# Program_Counter.net
KiCad netlist of a schematic drawn in Altium Designer
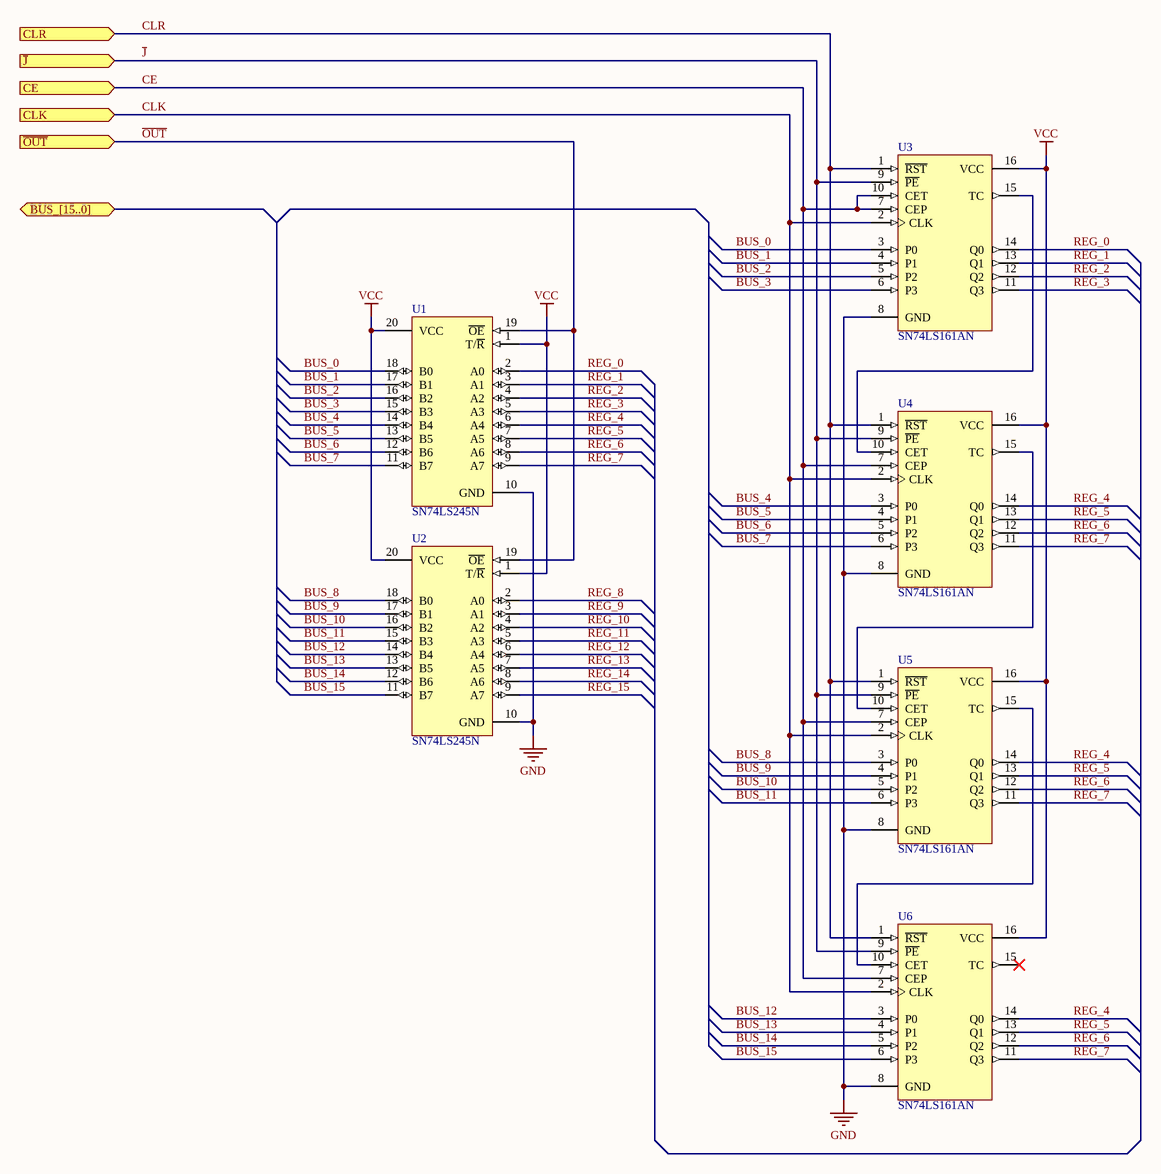
[diagram p0: Program_Counter.SchDoc]

(export (version "E")
  (design (tool "Eeschema 10.0.6"))
  (components
    (comp (ref "U1")
      (value "SN74LS245N")
      (footprint "N020")
      (description "Octal Bus Transceiver with 3-State Outputs")
      (fields (field (name "PUBLISHER") "Altium Limited"))
      (libsource (lib "TI Interface 8-Bit Line Transceiver") (part "SN74LS245N"))
    )
    (comp (ref "U2")
      (value "SN74LS245N")
      (footprint "N020")
      (description "Octal Bus Transceiver with 3-State Outputs")
      (fields (field (name "PUBLISHER") "Altium Limited"))
      (libsource (lib "TI Interface 8-Bit Line Transceiver") (part "SN74LS245N"))
    )
    (comp (ref "U3")
      (value "SN74LS161AN")
      (footprint "N016")
      (description "Synchronous 4-Bit Counter")
      (fields (field (name "PUBLISHER") "Altium Limited"))
      (libsource (lib "TI Logic Counter") (part "SN74LS161AN"))
    )
    (comp (ref "U4")
      (value "SN74LS161AN")
      (footprint "N016")
      (description "Synchronous 4-Bit Counter")
      (fields (field (name "PUBLISHER") "Altium Limited"))
      (libsource (lib "TI Logic Counter") (part "SN74LS161AN"))
    )
    (comp (ref "U5")
      (value "SN74LS161AN")
      (footprint "N016")
      (description "Synchronous 4-Bit Counter")
      (fields (field (name "PUBLISHER") "Altium Limited"))
      (libsource (lib "TI Logic Counter") (part "SN74LS161AN"))
    )
    (comp (ref "U6")
      (value "SN74LS161AN")
      (footprint "N016")
      (description "Synchronous 4-Bit Counter")
      (fields (field (name "PUBLISHER") "Altium Limited"))
      (libsource (lib "TI Logic Counter") (part "SN74LS161AN"))
    )
  )
  (nets
    (net (code "1") (name "/BUS_0") (class "Default")
      (node (ref "U1") (pin "18") (pinfunction "B0_18") (pintype "bidirectional"))
      (node (ref "U3") (pin "3") (pinfunction "P0_3") (pintype "input"))
    )
    (net (code "2") (name "/BUS_1") (class "Default")
      (node (ref "U1") (pin "17") (pinfunction "B1_17") (pintype "bidirectional"))
      (node (ref "U3") (pin "4") (pinfunction "P1_4") (pintype "input"))
    )
    (net (code "3") (name "/BUS_2") (class "Default")
      (node (ref "U1") (pin "16") (pinfunction "B2_16") (pintype "bidirectional"))
      (node (ref "U3") (pin "5") (pinfunction "P2_5") (pintype "input"))
    )
    (net (code "4") (name "/BUS_3") (class "Default")
      (node (ref "U1") (pin "15") (pinfunction "B3_15") (pintype "bidirectional"))
      (node (ref "U3") (pin "6") (pinfunction "P3_6") (pintype "input"))
    )
    (net (code "5") (name "/BUS_4") (class "Default")
      (node (ref "U1") (pin "14") (pinfunction "B4_14") (pintype "bidirectional"))
      (node (ref "U4") (pin "3") (pinfunction "P0_3") (pintype "input"))
    )
    (net (code "6") (name "/BUS_5") (class "Default")
      (node (ref "U1") (pin "13") (pinfunction "B5_13") (pintype "bidirectional"))
      (node (ref "U4") (pin "4") (pinfunction "P1_4") (pintype "input"))
    )
    (net (code "7") (name "/BUS_6") (class "Default")
      (node (ref "U1") (pin "12") (pinfunction "B6_12") (pintype "bidirectional"))
      (node (ref "U4") (pin "5") (pinfunction "P2_5") (pintype "input"))
    )
    (net (code "8") (name "/BUS_7") (class "Default")
      (node (ref "U1") (pin "11") (pinfunction "B7_11") (pintype "bidirectional"))
      (node (ref "U4") (pin "6") (pinfunction "P3_6") (pintype "input"))
    )
    (net (code "9") (name "/BUS_8") (class "Default")
      (node (ref "U2") (pin "18") (pinfunction "B0_18") (pintype "bidirectional"))
      (node (ref "U5") (pin "3") (pinfunction "P0_3") (pintype "input"))
    )
    (net (code "10") (name "/BUS_9") (class "Default")
      (node (ref "U2") (pin "17") (pinfunction "B1_17") (pintype "bidirectional"))
      (node (ref "U5") (pin "4") (pinfunction "P1_4") (pintype "input"))
    )
    (net (code "11") (name "/BUS_10") (class "Default")
      (node (ref "U2") (pin "16") (pinfunction "B2_16") (pintype "bidirectional"))
      (node (ref "U5") (pin "5") (pinfunction "P2_5") (pintype "input"))
    )
    (net (code "12") (name "/BUS_11") (class "Default")
      (node (ref "U2") (pin "15") (pinfunction "B3_15") (pintype "bidirectional"))
      (node (ref "U5") (pin "6") (pinfunction "P3_6") (pintype "input"))
    )
    (net (code "13") (name "/BUS_12") (class "Default")
      (node (ref "U2") (pin "14") (pinfunction "B4_14") (pintype "bidirectional"))
      (node (ref "U6") (pin "3") (pinfunction "P0_3") (pintype "input"))
    )
    (net (code "14") (name "/BUS_13") (class "Default")
      (node (ref "U2") (pin "13") (pinfunction "B5_13") (pintype "bidirectional"))
      (node (ref "U6") (pin "4") (pinfunction "P1_4") (pintype "input"))
    )
    (net (code "15") (name "/BUS_14") (class "Default")
      (node (ref "U2") (pin "12") (pinfunction "B6_12") (pintype "bidirectional"))
      (node (ref "U6") (pin "5") (pinfunction "P2_5") (pintype "input"))
    )
    (net (code "16") (name "/BUS_15") (class "Default")
      (node (ref "U2") (pin "11") (pinfunction "B7_11") (pintype "bidirectional"))
      (node (ref "U6") (pin "6") (pinfunction "P3_6") (pintype "input"))
    )
    (net (code "18") (name "/CE") (class "Default")
      (node (ref "U3") (pin "10") (pinfunction "CET_10") (pintype "input"))
      (node (ref "U3") (pin "7") (pinfunction "CEP_7") (pintype "input"))
      (node (ref "U4") (pin "7") (pinfunction "CEP_7") (pintype "input"))
      (node (ref "U5") (pin "7") (pinfunction "CEP_7") (pintype "input"))
      (node (ref "U6") (pin "7") (pinfunction "CEP_7") (pintype "input"))
    )
    (net (code "19") (name "/CLK") (class "Default")
      (node (ref "U3") (pin "2") (pinfunction "CLK_2") (pintype "input"))
      (node (ref "U4") (pin "2") (pinfunction "CLK_2") (pintype "input"))
      (node (ref "U5") (pin "2") (pinfunction "CLK_2") (pintype "input"))
      (node (ref "U6") (pin "2") (pinfunction "CLK_2") (pintype "input"))
    )
    (net (code "20") (name "/CLR") (class "Default")
      (node (ref "U3") (pin "1") (pinfunction "~{RST}_1") (pintype "input"))
      (node (ref "U4") (pin "1") (pinfunction "~{RST}_1") (pintype "input"))
      (node (ref "U5") (pin "1") (pinfunction "~{RST}_1") (pintype "input"))
      (node (ref "U6") (pin "1") (pinfunction "~{RST}_1") (pintype "input"))
    )
    (net (code "21") (name "/REG_0") (class "Default")
      (node (ref "U1") (pin "2") (pinfunction "A0_2") (pintype "bidirectional"))
      (node (ref "U3") (pin "14") (pinfunction "Q0_14") (pintype "output"))
    )
    (net (code "22") (name "/REG_1") (class "Default")
      (node (ref "U1") (pin "3") (pinfunction "A1_3") (pintype "bidirectional"))
      (node (ref "U3") (pin "13") (pinfunction "Q1_13") (pintype "output"))
    )
    (net (code "23") (name "/REG_2") (class "Default")
      (node (ref "U1") (pin "4") (pinfunction "A2_4") (pintype "bidirectional"))
      (node (ref "U3") (pin "12") (pinfunction "Q2_12") (pintype "output"))
    )
    (net (code "24") (name "/REG_3") (class "Default")
      (node (ref "U1") (pin "5") (pinfunction "A3_5") (pintype "bidirectional"))
      (node (ref "U3") (pin "11") (pinfunction "Q3_11") (pintype "output"))
    )
    (net (code "25") (name "/REG_4") (class "Default")
      (node (ref "U1") (pin "6") (pinfunction "A4_6") (pintype "bidirectional"))
      (node (ref "U4") (pin "14") (pinfunction "Q0_14") (pintype "output"))
      (node (ref "U5") (pin "14") (pinfunction "Q0_14") (pintype "output"))
      (node (ref "U6") (pin "14") (pinfunction "Q0_14") (pintype "output"))
    )
    (net (code "26") (name "/REG_5") (class "Default")
      (node (ref "U1") (pin "7") (pinfunction "A5_7") (pintype "bidirectional"))
      (node (ref "U4") (pin "13") (pinfunction "Q1_13") (pintype "output"))
      (node (ref "U5") (pin "13") (pinfunction "Q1_13") (pintype "output"))
      (node (ref "U6") (pin "13") (pinfunction "Q1_13") (pintype "output"))
    )
    (net (code "27") (name "/REG_6") (class "Default")
      (node (ref "U1") (pin "8") (pinfunction "A6_8") (pintype "bidirectional"))
      (node (ref "U4") (pin "12") (pinfunction "Q2_12") (pintype "output"))
      (node (ref "U5") (pin "12") (pinfunction "Q2_12") (pintype "output"))
      (node (ref "U6") (pin "12") (pinfunction "Q2_12") (pintype "output"))
    )
    (net (code "28") (name "/REG_7") (class "Default")
      (node (ref "U1") (pin "9") (pinfunction "A7_9") (pintype "bidirectional"))
      (node (ref "U4") (pin "11") (pinfunction "Q3_11") (pintype "output"))
      (node (ref "U5") (pin "11") (pinfunction "Q3_11") (pintype "output"))
      (node (ref "U6") (pin "11") (pinfunction "Q3_11") (pintype "output"))
    )
    (net (code "29") (name "/REG_8") (class "Default")
      (node (ref "U2") (pin "2") (pinfunction "A0_2") (pintype "bidirectional"))
    )
    (net (code "30") (name "/REG_9") (class "Default")
      (node (ref "U2") (pin "3") (pinfunction "A1_3") (pintype "bidirectional"))
    )
    (net (code "31") (name "/REG_10") (class "Default")
      (node (ref "U2") (pin "4") (pinfunction "A2_4") (pintype "bidirectional"))
    )
    (net (code "32") (name "/REG_11") (class "Default")
      (node (ref "U2") (pin "5") (pinfunction "A3_5") (pintype "bidirectional"))
    )
    (net (code "33") (name "/REG_12") (class "Default")
      (node (ref "U2") (pin "6") (pinfunction "A4_6") (pintype "bidirectional"))
    )
    (net (code "34") (name "/REG_13") (class "Default")
      (node (ref "U2") (pin "7") (pinfunction "A5_7") (pintype "bidirectional"))
    )
    (net (code "35") (name "/REG_14") (class "Default")
      (node (ref "U2") (pin "8") (pinfunction "A6_8") (pintype "bidirectional"))
    )
    (net (code "36") (name "/REG_15") (class "Default")
      (node (ref "U2") (pin "9") (pinfunction "A7_9") (pintype "bidirectional"))
    )
    (net (code "37") (name "/~{J}") (class "Default")
      (node (ref "U3") (pin "9") (pinfunction "~{PE}_9") (pintype "input"))
      (node (ref "U4") (pin "9") (pinfunction "~{PE}_9") (pintype "input"))
      (node (ref "U5") (pin "9") (pinfunction "~{PE}_9") (pintype "input"))
      (node (ref "U6") (pin "9") (pinfunction "~{PE}_9") (pintype "input"))
    )
    (net (code "38") (name "/~{OUT}") (class "Default")
      (node (ref "U1") (pin "19") (pinfunction "~{OE}_19") (pintype "input"))
      (node (ref "U2") (pin "19") (pinfunction "~{OE}_19") (pintype "input"))
    )
    (net (code "39") (name "GND") (class "Default")
      (node (ref "U1") (pin "10") (pinfunction "GND_10") (pintype "power_in"))
      (node (ref "U2") (pin "10") (pinfunction "GND_10") (pintype "power_in"))
      (node (ref "U3") (pin "8") (pinfunction "GND_8") (pintype "power_in"))
      (node (ref "U4") (pin "8") (pinfunction "GND_8") (pintype "power_in"))
      (node (ref "U5") (pin "8") (pinfunction "GND_8") (pintype "power_in"))
      (node (ref "U6") (pin "8") (pinfunction "GND_8") (pintype "power_in"))
    )
    (net (code "40") (name "Net-(U3-TC)") (class "Default")
      (node (ref "U3") (pin "15") (pinfunction "TC_15") (pintype "output"))
      (node (ref "U4") (pin "10") (pinfunction "CET_10") (pintype "input"))
    )
    (net (code "41") (name "Net-(U4-TC)") (class "Default")
      (node (ref "U4") (pin "15") (pinfunction "TC_15") (pintype "output"))
      (node (ref "U5") (pin "10") (pinfunction "CET_10") (pintype "input"))
    )
    (net (code "42") (name "Net-(U5-TC)") (class "Default")
      (node (ref "U5") (pin "15") (pinfunction "TC_15") (pintype "output"))
      (node (ref "U6") (pin "10") (pinfunction "CET_10") (pintype "input"))
    )
    (net (code "43") (name "VCC") (class "Default")
      (node (ref "U1") (pin "1") (pinfunction "T/~{R}_1") (pintype "input"))
      (node (ref "U1") (pin "20") (pinfunction "VCC_20") (pintype "power_in"))
      (node (ref "U2") (pin "1") (pinfunction "T/~{R}_1") (pintype "input"))
      (node (ref "U2") (pin "20") (pinfunction "VCC_20") (pintype "power_in"))
      (node (ref "U3") (pin "16") (pinfunction "VCC_16") (pintype "power_in"))
      (node (ref "U4") (pin "16") (pinfunction "VCC_16") (pintype "power_in"))
      (node (ref "U5") (pin "16") (pinfunction "VCC_16") (pintype "power_in"))
      (node (ref "U6") (pin "16") (pinfunction "VCC_16") (pintype "power_in"))
    )
    (net (code "44") (name "unconnected-(U6-TC-Pad15)") (class "Default")
      (node (ref "U6") (pin "15") (pinfunction "TC_15") (pintype "output+no_connect"))
    )
  )
)
